# STorM32_NT_BGC_v330m.net
KiCad netlist of a schematic drawn in EAGLE
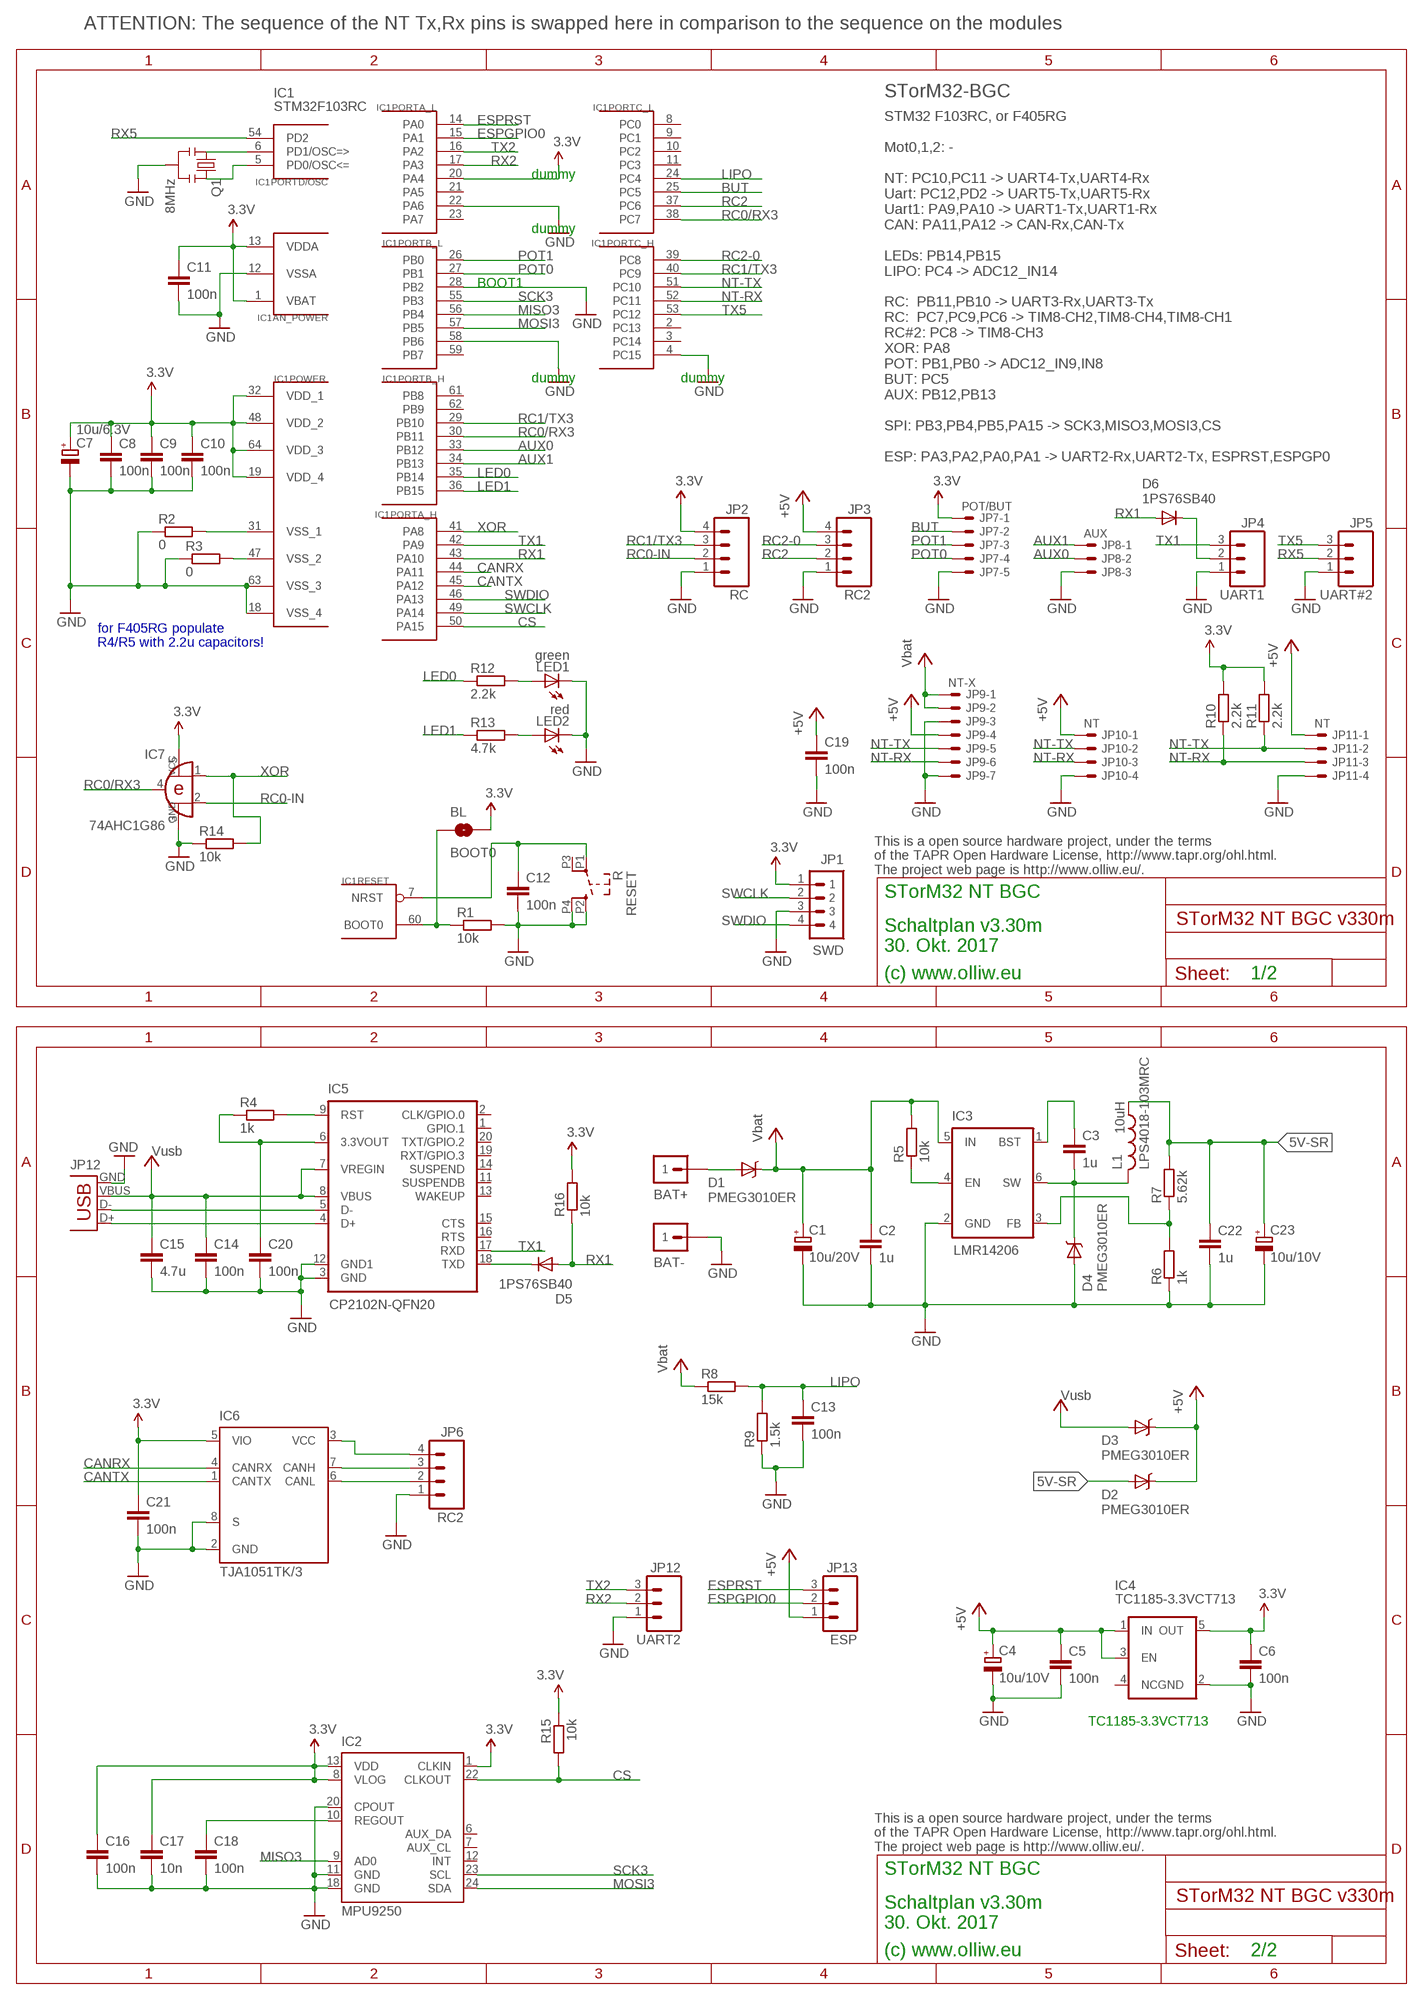
[diagram p0: schematic, sheet 1]

(export (version "E")
  (design (tool "Eeschema 10.0.6"))
  (components
    (comp (ref "BAT+")
      (value "M1X1")
      (footprint "eagle-import:1X1_WITHOUT")
      (libsource (lib "eagle-import") (part "M1X1"))
    )
    (comp (ref "BAT-")
      (value "M1X1")
      (footprint "eagle-import:1X1_WITHOUT")
      (libsource (lib "eagle-import") (part "M1X1"))
    )
    (comp (ref "BL")
      (value "BOOT0")
      (footprint "eagle-import:SJ_2S-NO")
      (libsource (lib "eagle-import") (part "SOLDERJUMPERNO"))
    )
    (comp (ref "C1")
      (value "10u/20V")
      (footprint "eagle-import:SMC_B")
      (libsource (lib "eagle-import") (part "CPOL-EUSMCB"))
    )
    (comp (ref "C2")
      (value "1u")
      (footprint "eagle-import:C0603")
      (libsource (lib "eagle-import") (part "C-EUC0603"))
    )
    (comp (ref "C3")
      (value "1u")
      (footprint "eagle-import:C0603")
      (libsource (lib "eagle-import") (part "C-EUC0603"))
    )
    (comp (ref "C4")
      (value "10u/10V")
      (footprint "eagle-import:SMC_A")
      (libsource (lib "eagle-import") (part "CPOL-EUSMCA"))
    )
    (comp (ref "C5")
      (value "100n")
      (footprint "eagle-import:C0603")
      (libsource (lib "eagle-import") (part "C-EUC0603"))
    )
    (comp (ref "C6")
      (value "100n")
      (footprint "eagle-import:C0402")
      (libsource (lib "eagle-import") (part "C-EUC0402"))
    )
    (comp (ref "C7")
      (value "10u/6.3V")
      (footprint "eagle-import:SMC_A")
      (libsource (lib "eagle-import") (part "CPOL-EUSMCA"))
    )
    (comp (ref "C8")
      (value "100n")
      (footprint "eagle-import:C0402")
      (libsource (lib "eagle-import") (part "C-EUC0402"))
    )
    (comp (ref "C9")
      (value "100n")
      (footprint "eagle-import:C0402")
      (libsource (lib "eagle-import") (part "C-EUC0402"))
    )
    (comp (ref "C10")
      (value "100n")
      (footprint "eagle-import:C0402")
      (libsource (lib "eagle-import") (part "C-EUC0402"))
    )
    (comp (ref "C11")
      (value "100n")
      (footprint "eagle-import:C0402")
      (libsource (lib "eagle-import") (part "C-EUC0402"))
    )
    (comp (ref "C12")
      (value "100n")
      (footprint "eagle-import:C0402")
      (libsource (lib "eagle-import") (part "C-EUC0402"))
    )
    (comp (ref "C13")
      (value "100n")
      (footprint "eagle-import:C0402")
      (libsource (lib "eagle-import") (part "C-EUC0402"))
    )
    (comp (ref "C14")
      (value "100n")
      (footprint "eagle-import:C0402")
      (libsource (lib "eagle-import") (part "C-EUC0402"))
    )
    (comp (ref "C15")
      (value "4.7u")
      (footprint "eagle-import:C0603")
      (libsource (lib "eagle-import") (part "C-EUC0603"))
    )
    (comp (ref "C16")
      (value "100n")
      (footprint "eagle-import:C0402")
      (libsource (lib "eagle-import") (part "C-EUC0402"))
    )
    (comp (ref "C17")
      (value "10n")
      (footprint "eagle-import:C0402")
      (libsource (lib "eagle-import") (part "C-EUC0402"))
    )
    (comp (ref "C18")
      (value "100n")
      (footprint "eagle-import:C0402")
      (libsource (lib "eagle-import") (part "C-EUC0402"))
    )
    (comp (ref "C19")
      (value "100n")
      (footprint "eagle-import:C0402")
      (libsource (lib "eagle-import") (part "C-EUC0402"))
    )
    (comp (ref "C20")
      (value "100n")
      (footprint "eagle-import:C0402")
      (libsource (lib "eagle-import") (part "C-EUC0402"))
    )
    (comp (ref "C21")
      (value "100n")
      (footprint "eagle-import:C0402")
      (libsource (lib "eagle-import") (part "C-EUC0402"))
    )
    (comp (ref "C22")
      (value "1u")
      (footprint "eagle-import:C0603")
      (libsource (lib "eagle-import") (part "C-EUC0603"))
    )
    (comp (ref "C23")
      (value "10u/10V")
      (footprint "eagle-import:SMC_A")
      (libsource (lib "eagle-import") (part "CPOL-EUSMCA"))
    )
    (comp (ref "D1")
      (value "PMEG3010ER")
      (footprint "eagle-import:SOD123W-DIODE")
      (libsource (lib "eagle-import") (part "DIODE-SCHOTTKYSOD123-W"))
    )
    (comp (ref "D2")
      (value "PMEG3010ER")
      (footprint "eagle-import:SOD123W-DIODE")
      (libsource (lib "eagle-import") (part "DIODE-SCHOTTKYSOD123-W"))
    )
    (comp (ref "D3")
      (value "PMEG3010ER")
      (footprint "eagle-import:SOD123W-DIODE")
      (libsource (lib "eagle-import") (part "DIODE-SCHOTTKYSOD123-W"))
    )
    (comp (ref "D4")
      (value "PMEG3010ER")
      (footprint "eagle-import:SOD123W-DIODE")
      (libsource (lib "eagle-import") (part "DIODE-SCHOTTKYSOD123-W"))
    )
    (comp (ref "D5")
      (value "1PS76SB40")
      (footprint "eagle-import:SOD110-R")
      (libsource (lib "eagle-import") (part "DIODE-SOD110-R"))
    )
    (comp (ref "D6")
      (value "1PS76SB40")
      (footprint "eagle-import:SOD110-R")
      (libsource (lib "eagle-import") (part "DIODE-SOD110-R"))
    )
    (comp (ref "IC1")
      (value "STM32F103RCT6")
      (footprint "eagle-import:TQFP64")
      (libsource (lib "eagle-import") (part "STM32F10XRXT6"))
    )
    (comp (ref "IC2")
      (value "MPU9250")
      (footprint "eagle-import:QFN-24-3X3")
      (libsource (lib "eagle-import") (part "IMU3000QFN-24-0.4MIL"))
    )
    (comp (ref "IC3")
      (value "LMR14206")
      (footprint "eagle-import:SOT23-6")
      (libsource (lib "eagle-import") (part "MP2359"))
    )
    (comp (ref "IC4")
      (value "TC1185-3.3VCT713")
      (footprint "eagle-import:SOT23-5")
      (libsource (lib "eagle-import") (part "V_REG_TPS76433SOT23-5"))
    )
    (comp (ref "IC5")
      (value "CP2102N-QFN20")
      (footprint "eagle-import:QFN20-CP2102N")
      (libsource (lib "eagle-import") (part "CP2102N-QFN20"))
    )
    (comp (ref "IC6")
      (value "TJA1051TK/3")
      (footprint "eagle-import:HVSON8")
      (libsource (lib "eagle-import") (part "TJA1051TK/3"))
    )
    (comp (ref "IC7")
      (value "74AHC1G86")
      (footprint "eagle-import:SOT23-5-VER1")
      (libsource (lib "eagle-import") (part "74AHC1G86"))
    )
    (comp (ref "JP1")
      (value "SWD")
      (footprint "eagle-import:4X1_1P27_OCT_BILEX")
      (libsource (lib "eagle-import") (part "P4X1_1P27-OCT_BILEX"))
    )
    (comp (ref "JP2")
      (value "RC")
      (footprint "eagle-import:1X04_NO_SILK")
      (libsource (lib "eagle-import") (part "M041X04_NO_SILK"))
    )
    (comp (ref "JP3")
      (value "RC2")
      (footprint "eagle-import:1X04_NO_SILK")
      (libsource (lib "eagle-import") (part "M041X04_NO_SILK"))
    )
    (comp (ref "JP4")
      (value "UART1")
      (footprint "eagle-import:1X03_NO_SILK")
      (libsource (lib "eagle-import") (part "M031X03_NO_SILK"))
    )
    (comp (ref "JP5")
      (value "UART#2")
      (footprint "eagle-import:1X03_NO_SILK")
      (libsource (lib "eagle-import") (part "M031X03_NO_SILK"))
    )
    (comp (ref "JP6")
      (value "RC2")
      (footprint "eagle-import:1X04_NO_SILK")
      (libsource (lib "eagle-import") (part "M041X04_NO_SILK"))
    )
    (comp (ref "JP7")
      (value "POT/BUT")
      (footprint "eagle-import:SM05B-SRSS-TB")
      (libsource (lib "eagle-import") (part "?M05B-SRSS-TBS"))
    )
    (comp (ref "JP8")
      (value "AUX")
      (footprint "eagle-import:SM03B-SRSS-TB")
      (libsource (lib "eagle-import") (part "?M03B-SRSS-TBS"))
    )
    (comp (ref "JP9")
      (value "NT-X")
      (footprint "eagle-import:SM07B-SRSS-TB")
      (libsource (lib "eagle-import") (part "?M07B-SRSS-TBS"))
    )
    (comp (ref "JP10")
      (value "NT")
      (footprint "eagle-import:SM04B-SRSS-TB")
      (libsource (lib "eagle-import") (part "?M04B-SRSS-TBS"))
    )
    (comp (ref "JP11")
      (value "NT")
      (footprint "eagle-import:SM04B-SRSS-TB")
      (libsource (lib "eagle-import") (part "?M04B-SRSS-TBS"))
    )
    (comp (ref "JP12")
      (value "UART2")
      (footprint "eagle-import:1X03_NO_SILK")
      (libsource (lib "eagle-import") (part "M031X03_NO_SILK"))
    )
    (comp (ref "JP13")
      (value "ESP")
      (footprint "eagle-import:1X03_NO_SILK")
      (libsource (lib "eagle-import") (part "M031X03_NO_SILK"))
    )
    (comp (ref "L1")
      (value "LPS4018-103MRC")
      (footprint "eagle-import:L4X4")
      (libsource (lib "eagle-import") (part "L"))
    )
    (comp (ref "LED1")
      (value "green")
      (footprint "eagle-import:CHIPLED_0603")
      (libsource (lib "eagle-import") (part "LEDCHIPLED_0603"))
    )
    (comp (ref "LED2")
      (value "red")
      (footprint "eagle-import:CHIPLED_0603")
      (libsource (lib "eagle-import") (part "LEDCHIPLED_0603"))
    )
    (comp (ref "Q1")
      (value "8MHz")
      (footprint "eagle-import:RESONATOR-SMD")
      (libsource (lib "eagle-import") (part "RESONATORSMD"))
    )
    (comp (ref "R1")
      (value "10k")
      (footprint "eagle-import:R0402")
      (libsource (lib "eagle-import") (part "R-EU_R0402"))
    )
    (comp (ref "R2")
      (value "0")
      (footprint "eagle-import:R0402")
      (libsource (lib "eagle-import") (part "R-EU_R0402"))
    )
    (comp (ref "R3")
      (value "0")
      (footprint "eagle-import:R0402")
      (libsource (lib "eagle-import") (part "R-EU_R0402"))
    )
    (comp (ref "R4")
      (value "1k")
      (footprint "eagle-import:R0402")
      (libsource (lib "eagle-import") (part "R-EU_R0402"))
    )
    (comp (ref "R5")
      (value "10k")
      (footprint "eagle-import:R0402")
      (libsource (lib "eagle-import") (part "R-EU_R0402"))
    )
    (comp (ref "R6")
      (value "1k")
      (footprint "eagle-import:R0402")
      (libsource (lib "eagle-import") (part "R-EU_R0402"))
    )
    (comp (ref "R7")
      (value "5.62k")
      (footprint "eagle-import:R0402")
      (libsource (lib "eagle-import") (part "R-EU_R0402"))
    )
    (comp (ref "R8")
      (value "15k")
      (footprint "eagle-import:R0402")
      (libsource (lib "eagle-import") (part "R-EU_R0402"))
    )
    (comp (ref "R9")
      (value "1.5k")
      (footprint "eagle-import:R0402")
      (libsource (lib "eagle-import") (part "R-EU_R0402"))
    )
    (comp (ref "R10")
      (value "2.2k")
      (footprint "eagle-import:R0402")
      (libsource (lib "eagle-import") (part "R-EU_R0402"))
    )
    (comp (ref "R11")
      (value "2.2k")
      (footprint "eagle-import:R0402")
      (libsource (lib "eagle-import") (part "R-EU_R0402"))
    )
    (comp (ref "R12")
      (value "2.2k")
      (footprint "eagle-import:R0402")
      (libsource (lib "eagle-import") (part "R-EU_R0402"))
    )
    (comp (ref "R13")
      (value "4.7k")
      (footprint "eagle-import:R0402")
      (libsource (lib "eagle-import") (part "R-EU_R0402"))
    )
    (comp (ref "R14")
      (value "10k")
      (footprint "eagle-import:R0402")
      (libsource (lib "eagle-import") (part "R-EU_R0402"))
    )
    (comp (ref "R15")
      (value "10k")
      (footprint "eagle-import:R0402")
      (libsource (lib "eagle-import") (part "R-EU_R0402"))
    )
    (comp (ref "R16")
      (value "10k")
      (footprint "eagle-import:R0402")
      (libsource (lib "eagle-import") (part "R-EU_R0402"))
    )
    (comp (ref "RESET")
      (value "R")
      (footprint "eagle-import:TACTILE-SWITCH-SMD-RIGHT-TL1014")
      (libsource (lib "eagle-import") (part "SWITCH-SMD-RIGHT-TL1014"))
    )
    (comp (ref "USB")
      (value "Amphenol 10118192-0001LF")
      (footprint "eagle-import:USB-MICROB")
      (libsource (lib "eagle-import") (part "USB-MICROB"))
    )
  )
  (nets
    (net (code "1") (name "+5V") (class "Default")
      (node (ref "C19") (pin "1") (pinfunction "1_1") (pintype "passive"))
      (node (ref "C4") (pin "+") (pinfunction "+_+") (pintype "passive"))
      (node (ref "C5") (pin "1") (pinfunction "1_1") (pintype "passive"))
      (node (ref "D2") (pin "C") (pinfunction "C_C") (pintype "passive"))
      (node (ref "D3") (pin "C") (pinfunction "C_C") (pintype "passive"))
      (node (ref "IC4") (pin "1") (pinfunction "IN_1") (pintype "power_in"))
      (node (ref "IC4") (pin "3") (pinfunction "EN_3") (pintype "input"))
      (node (ref "JP10") (pin "1") (pinfunction "S_1") (pintype "passive"))
      (node (ref "JP11") (pin "1") (pinfunction "S_1") (pintype "passive"))
      (node (ref "JP13") (pin "1") (pinfunction "1_1") (pintype "passive"))
      (node (ref "JP3") (pin "4") (pinfunction "4_4") (pintype "passive"))
      (node (ref "JP9") (pin "4") (pinfunction "S_4") (pintype "passive"))
    )
    (net (code "2") (name "/AUX0") (class "Default")
      (node (ref "IC1") (pin "33") (pinfunction "PB12_33") (pintype "bidirectional"))
      (node (ref "JP8") (pin "2") (pinfunction "S_2") (pintype "passive"))
    )
    (net (code "3") (name "/AUX1") (class "Default")
      (node (ref "IC1") (pin "34") (pinfunction "PB13_34") (pintype "bidirectional"))
      (node (ref "JP8") (pin "1") (pinfunction "S_1") (pintype "passive"))
    )
    (net (code "4") (name "/BUT") (class "Default")
      (node (ref "IC1") (pin "25") (pinfunction "PC5_25") (pintype "bidirectional"))
      (node (ref "JP7") (pin "2") (pinfunction "S_2") (pintype "passive"))
    )
    (net (code "5") (name "/CANRX") (class "Default")
      (node (ref "IC1") (pin "44") (pinfunction "PA11_44") (pintype "bidirectional"))
      (node (ref "IC6") (pin "4") (pinfunction "CANRX_4") (pintype "output"))
    )
    (net (code "6") (name "/CANTX") (class "Default")
      (node (ref "IC1") (pin "45") (pinfunction "PA12_45") (pintype "bidirectional"))
      (node (ref "IC6") (pin "1") (pinfunction "CANTX_1") (pintype "input"))
    )
    (net (code "7") (name "/CS") (class "Default")
      (node (ref "IC1") (pin "50") (pinfunction "PA15_50") (pintype "bidirectional"))
      (node (ref "IC2") (pin "22") (pinfunction "CLKOUT_22") (pintype "bidirectional"))
      (node (ref "R15") (pin "2") (pinfunction "2_2") (pintype "passive"))
    )
    (net (code "8") (name "/ESPGPIO0") (class "Default")
      (node (ref "IC1") (pin "15") (pinfunction "PA1_15") (pintype "bidirectional"))
      (node (ref "JP13") (pin "2") (pinfunction "2_2") (pintype "passive"))
    )
    (net (code "9") (name "/ESPRST") (class "Default")
      (node (ref "IC1") (pin "14") (pinfunction "PA0_14") (pintype "bidirectional"))
      (node (ref "JP13") (pin "3") (pinfunction "3_3") (pintype "passive"))
    )
    (net (code "10") (name "/LED0") (class "Default")
      (node (ref "IC1") (pin "35") (pinfunction "PB14_35") (pintype "bidirectional"))
      (node (ref "R12") (pin "1") (pinfunction "1_1") (pintype "passive"))
    )
    (net (code "11") (name "/LED1") (class "Default")
      (node (ref "IC1") (pin "36") (pinfunction "PB15_36") (pintype "bidirectional"))
      (node (ref "R13") (pin "1") (pinfunction "1_1") (pintype "passive"))
    )
    (net (code "12") (name "/LIPO") (class "Default")
      (node (ref "C13") (pin "1") (pinfunction "1_1") (pintype "passive"))
      (node (ref "IC1") (pin "24") (pinfunction "PC4_24") (pintype "bidirectional"))
      (node (ref "R8") (pin "2") (pinfunction "2_2") (pintype "passive"))
      (node (ref "R9") (pin "2") (pinfunction "2_2") (pintype "passive"))
    )
    (net (code "13") (name "/MISO3") (class "Default")
      (node (ref "IC1") (pin "56") (pinfunction "PB4_56") (pintype "bidirectional"))
      (node (ref "IC2") (pin "9") (pinfunction "AD0_9") (pintype "bidirectional"))
    )
    (net (code "14") (name "/MOSI3") (class "Default")
      (node (ref "IC1") (pin "57") (pinfunction "PB5_57") (pintype "bidirectional"))
      (node (ref "IC2") (pin "24") (pinfunction "SDA_24") (pintype "bidirectional"))
    )
    (net (code "15") (name "/NT-RX") (class "Default")
      (node (ref "IC1") (pin "52") (pinfunction "PC11_52") (pintype "bidirectional"))
      (node (ref "JP10") (pin "3") (pinfunction "S_3") (pintype "passive"))
      (node (ref "JP11") (pin "3") (pinfunction "S_3") (pintype "passive"))
      (node (ref "JP9") (pin "6") (pinfunction "S_6") (pintype "passive"))
      (node (ref "R10") (pin "1") (pinfunction "1_1") (pintype "passive"))
    )
    (net (code "16") (name "/NT-TX") (class "Default")
      (node (ref "IC1") (pin "51") (pinfunction "PC10_51") (pintype "bidirectional"))
      (node (ref "JP10") (pin "2") (pinfunction "S_2") (pintype "passive"))
      (node (ref "JP11") (pin "2") (pinfunction "S_2") (pintype "passive"))
      (node (ref "JP9") (pin "5") (pinfunction "S_5") (pintype "passive"))
      (node (ref "R11") (pin "1") (pinfunction "1_1") (pintype "passive"))
    )
    (net (code "17") (name "/POT0") (class "Default")
      (node (ref "IC1") (pin "27") (pinfunction "PB1_27") (pintype "bidirectional"))
      (node (ref "JP7") (pin "4") (pinfunction "S_4") (pintype "passive"))
    )
    (net (code "18") (name "/POT1") (class "Default")
      (node (ref "IC1") (pin "26") (pinfunction "PB0_26") (pintype "bidirectional"))
      (node (ref "JP7") (pin "3") (pinfunction "S_3") (pintype "passive"))
    )
    (net (code "19") (name "/RC0-IN") (class "Default")
      (node (ref "IC7") (pin "2") (pinfunction "I1_2") (pintype "input"))
      (node (ref "JP2") (pin "2") (pinfunction "2_2") (pintype "passive"))
    )
    (net (code "20") (name "/RC0{slash}RX3") (class "Default")
      (node (ref "IC1") (pin "30") (pinfunction "PB11_30") (pintype "bidirectional"))
      (node (ref "IC1") (pin "38") (pinfunction "PC7_38") (pintype "bidirectional"))
      (node (ref "IC7") (pin "4") (pinfunction "O_4") (pintype "output"))
    )
    (net (code "21") (name "/RC1{slash}TX3") (class "Default")
      (node (ref "IC1") (pin "29") (pinfunction "PB10_29") (pintype "bidirectional"))
      (node (ref "IC1") (pin "40") (pinfunction "PC9_40") (pintype "bidirectional"))
      (node (ref "JP2") (pin "3") (pinfunction "3_3") (pintype "passive"))
    )
    (net (code "22") (name "/RC2") (class "Default")
      (node (ref "IC1") (pin "37") (pinfunction "PC6_37") (pintype "bidirectional"))
      (node (ref "JP3") (pin "2") (pinfunction "2_2") (pintype "passive"))
    )
    (net (code "23") (name "/RC2-0") (class "Default")
      (node (ref "IC1") (pin "39") (pinfunction "PC8_39") (pintype "bidirectional"))
      (node (ref "JP3") (pin "3") (pinfunction "3_3") (pintype "passive"))
    )
    (net (code "24") (name "/RX1") (class "Default")
      (node (ref "D5") (pin "A") (pinfunction "A_A") (pintype "passive"))
      (node (ref "D6") (pin "A") (pinfunction "A_A") (pintype "passive"))
      (node (ref "IC1") (pin "43") (pinfunction "PA10_43") (pintype "bidirectional"))
      (node (ref "R16") (pin "1") (pinfunction "1_1") (pintype "passive"))
    )
    (net (code "25") (name "/RX2") (class "Default")
      (node (ref "IC1") (pin "17") (pinfunction "PA3_17") (pintype "bidirectional"))
      (node (ref "JP12") (pin "2") (pinfunction "2_2") (pintype "passive"))
    )
    (net (code "26") (name "/RX5") (class "Default")
      (node (ref "IC1") (pin "54") (pinfunction "PD2_54") (pintype "bidirectional"))
      (node (ref "JP5") (pin "2") (pinfunction "2_2") (pintype "passive"))
    )
    (net (code "27") (name "/SCK3") (class "Default")
      (node (ref "IC1") (pin "55") (pinfunction "PB3_55") (pintype "bidirectional"))
      (node (ref "IC2") (pin "23") (pinfunction "SCL_23") (pintype "bidirectional"))
    )
    (net (code "28") (name "/SWCLK") (class "Default")
      (node (ref "IC1") (pin "49") (pinfunction "PA14_49") (pintype "bidirectional"))
      (node (ref "JP1") (pin "2") (pinfunction "2_2") (pintype "passive"))
    )
    (net (code "29") (name "/SWDIO") (class "Default")
      (node (ref "IC1") (pin "46") (pinfunction "PA13_46") (pintype "bidirectional"))
      (node (ref "JP1") (pin "4") (pinfunction "4_4") (pintype "passive"))
    )
    (net (code "30") (name "/TX1") (class "Default")
      (node (ref "IC1") (pin "42") (pinfunction "PA9_42") (pintype "bidirectional"))
      (node (ref "IC5") (pin "17") (pinfunction "RXD_17") (pintype "input"))
      (node (ref "JP4") (pin "3") (pinfunction "3_3") (pintype "passive"))
    )
    (net (code "31") (name "/TX2") (class "Default")
      (node (ref "IC1") (pin "16") (pinfunction "PA2_16") (pintype "bidirectional"))
      (node (ref "JP12") (pin "3") (pinfunction "3_3") (pintype "passive"))
    )
    (net (code "32") (name "/TX5") (class "Default")
      (node (ref "IC1") (pin "53") (pinfunction "PC12_53") (pintype "bidirectional"))
      (node (ref "JP5") (pin "3") (pinfunction "3_3") (pintype "passive"))
    )
    (net (code "33") (name "/XOR") (class "Default")
      (node (ref "IC1") (pin "41") (pinfunction "PA8_41") (pintype "bidirectional"))
      (node (ref "IC7") (pin "1") (pinfunction "I0_1") (pintype "input"))
      (node (ref "R14") (pin "2") (pinfunction "2_2") (pintype "passive"))
    )
    (net (code "34") (name "3.3V") (class "Default")
      (node (ref "BL") (pin "2") (pinfunction "2_2") (pintype "passive"))
      (node (ref "C10") (pin "1") (pinfunction "1_1") (pintype "passive"))
      (node (ref "C11") (pin "1") (pinfunction "1_1") (pintype "passive"))
      (node (ref "C16") (pin "1") (pinfunction "1_1") (pintype "passive"))
      (node (ref "C17") (pin "1") (pinfunction "1_1") (pintype "passive"))
      (node (ref "C21") (pin "1") (pinfunction "1_1") (pintype "passive"))
      (node (ref "C6") (pin "1") (pinfunction "1_1") (pintype "passive"))
      (node (ref "C7") (pin "+") (pinfunction "+_+") (pintype "passive"))
      (node (ref "C8") (pin "1") (pinfunction "1_1") (pintype "passive"))
      (node (ref "C9") (pin "1") (pinfunction "1_1") (pintype "passive"))
      (node (ref "IC1") (pin "1") (pinfunction "VBAT_1") (pintype "power_in"))
      (node (ref "IC1") (pin "13") (pinfunction "VDDA_13") (pintype "power_in"))
      (node (ref "IC1") (pin "19") (pinfunction "VDD_4_19") (pintype "power_in"))
      (node (ref "IC1") (pin "20") (pinfunction "PA4_20") (pintype "bidirectional"))
      (node (ref "IC1") (pin "32") (pinfunction "VDD_1_32") (pintype "power_in"))
      (node (ref "IC1") (pin "48") (pinfunction "VDD_2_48") (pintype "power_in"))
      (node (ref "IC1") (pin "64") (pinfunction "VDD_3_64") (pintype "power_in"))
      (node (ref "IC2") (pin "1") (pinfunction "CLKIN_1") (pintype "bidirectional"))
      (node (ref "IC2") (pin "13") (pinfunction "VDD_13") (pintype "bidirectional"))
      (node (ref "IC2") (pin "8") (pinfunction "VLOG_8") (pintype "bidirectional"))
      (node (ref "IC4") (pin "5") (pinfunction "OUT_5") (pintype "output"))
      (node (ref "IC6") (pin "5") (pinfunction "VIO_5") (pintype "power_in"))
      (node (ref "IC7") (pin "5") (pinfunction "VCC_5") (pintype "power_in"))
      (node (ref "JP1") (pin "1") (pinfunction "1_1") (pintype "passive"))
      (node (ref "JP2") (pin "4") (pinfunction "4_4") (pintype "passive"))
      (node (ref "JP7") (pin "1") (pinfunction "S_1") (pintype "passive"))
      (node (ref "R10") (pin "2") (pinfunction "2_2") (pintype "passive"))
      (node (ref "R11") (pin "2") (pinfunction "2_2") (pintype "passive"))
      (node (ref "R15") (pin "1") (pinfunction "1_1") (pintype "passive"))
      (node (ref "R16") (pin "2") (pinfunction "2_2") (pintype "passive"))
    )
    (net (code "35") (name "5V-SR") (class "Default")
      (node (ref "C22") (pin "1") (pinfunction "1_1") (pintype "passive"))
      (node (ref "C23") (pin "+") (pinfunction "+_+") (pintype "passive"))
      (node (ref "D2") (pin "A") (pinfunction "A_A") (pintype "passive"))
      (node (ref "L1") (pin "1") (pinfunction "1_1") (pintype "passive"))
      (node (ref "R7") (pin "2") (pinfunction "2_2") (pintype "passive"))
    )
    (net (code "36") (name "GND") (class "Default")
      (node (ref "BAT-") (pin "1") (pinfunction "1_1") (pintype "passive"))
      (node (ref "C1") (pin "-") (pinfunction "-_-") (pintype "passive"))
      (node (ref "C10") (pin "2") (pinfunction "2_2") (pintype "passive"))
      (node (ref "C11") (pin "2") (pinfunction "2_2") (pintype "passive"))
      (node (ref "C12") (pin "2") (pinfunction "2_2") (pintype "passive"))
      (node (ref "C13") (pin "2") (pinfunction "2_2") (pintype "passive"))
      (node (ref "C14") (pin "2") (pinfunction "2_2") (pintype "passive"))
      (node (ref "C15") (pin "2") (pinfunction "2_2") (pintype "passive"))
      (node (ref "C16") (pin "2") (pinfunction "2_2") (pintype "passive"))
      (node (ref "C17") (pin "2") (pinfunction "2_2") (pintype "passive"))
      (node (ref "C18") (pin "2") (pinfunction "2_2") (pintype "passive"))
      (node (ref "C19") (pin "2") (pinfunction "2_2") (pintype "passive"))
      (node (ref "C2") (pin "2") (pinfunction "2_2") (pintype "passive"))
      (node (ref "C20") (pin "2") (pinfunction "2_2") (pintype "passive"))
      (node (ref "C21") (pin "2") (pinfunction "2_2") (pintype "passive"))
      (node (ref "C22") (pin "2") (pinfunction "2_2") (pintype "passive"))
      (node (ref "C23") (pin "-") (pinfunction "-_-") (pintype "passive"))
      (node (ref "C4") (pin "-") (pinfunction "-_-") (pintype "passive"))
      (node (ref "C5") (pin "2") (pinfunction "2_2") (pintype "passive"))
      (node (ref "C6") (pin "2") (pinfunction "2_2") (pintype "passive"))
      (node (ref "C7") (pin "-") (pinfunction "-_-") (pintype "passive"))
      (node (ref "C8") (pin "2") (pinfunction "2_2") (pintype "passive"))
      (node (ref "C9") (pin "2") (pinfunction "2_2") (pintype "passive"))
      (node (ref "D4") (pin "A") (pinfunction "A_A") (pintype "passive"))
      (node (ref "IC1") (pin "12") (pinfunction "VSSA_12") (pintype "power_in"))
      (node (ref "IC1") (pin "18") (pinfunction "VSS_4_18") (pintype "power_in"))
      (node (ref "IC1") (pin "22") (pinfunction "PA6_22") (pintype "bidirectional"))
      (node (ref "IC1") (pin "28") (pinfunction "PB2_28") (pintype "bidirectional"))
      (node (ref "IC1") (pin "4") (pinfunction "PC15_4") (pintype "bidirectional"))
      (node (ref "IC1") (pin "58") (pinfunction "PB6_58") (pintype "bidirectional"))
      (node (ref "IC1") (pin "63") (pinfunction "VSS_3_63") (pintype "power_in"))
      (node (ref "IC2") (pin "11") (pinfunction "GND_11") (pintype "bidirectional"))
      (node (ref "IC2") (pin "18") (pinfunction "GND_18") (pintype "bidirectional"))
      (node (ref "IC2") (pin "20") (pinfunction "CPOUT_20") (pintype "bidirectional"))
      (node (ref "IC3") (pin "2") (pinfunction "GND_2") (pintype "power_in"))
      (node (ref "IC4") (pin "2") (pinfunction "GND_2") (pintype "power_in"))
      (node (ref "IC5") (pin "12") (pinfunction "GND1_12") (pintype "power_in"))
      (node (ref "IC5") (pin "3") (pinfunction "GND_3") (pintype "power_in"))
      (node (ref "IC6") (pin "2") (pinfunction "GND_2") (pintype "power_in"))
      (node (ref "IC6") (pin "8") (pinfunction "S_8") (pintype "input"))
      (node (ref "IC7") (pin "3") (pinfunction "GND_3") (pintype "power_in"))
      (node (ref "JP1") (pin "3") (pinfunction "3_3") (pintype "passive"))
      (node (ref "JP10") (pin "4") (pinfunction "S_4") (pintype "passive"))
      (node (ref "JP11") (pin "4") (pinfunction "S_4") (pintype "passive"))
      (node (ref "JP12") (pin "1") (pinfunction "1_1") (pintype "passive"))
      (node (ref "JP2") (pin "1") (pinfunction "1_1") (pintype "passive"))
      (node (ref "JP3") (pin "1") (pinfunction "1_1") (pintype "passive"))
      (node (ref "JP4") (pin "1") (pinfunction "1_1") (pintype "passive"))
      (node (ref "JP5") (pin "1") (pinfunction "1_1") (pintype "passive"))
      (node (ref "JP6") (pin "1") (pinfunction "1_1") (pintype "passive"))
      (node (ref "JP7") (pin "5") (pinfunction "S_5") (pintype "passive"))
      (node (ref "JP8") (pin "3") (pinfunction "S_3") (pintype "passive"))
      (node (ref "JP9") (pin "3") (pinfunction "S_3") (pintype "passive"))
      (node (ref "JP9") (pin "7") (pinfunction "S_7") (pintype "passive"))
      (node (ref "LED1") (pin "C") (pinfunction "C_C") (pintype "passive"))
      (node (ref "LED2") (pin "C") (pinfunction "C_C") (pintype "passive"))
      (node (ref "Q1") (pin "2") (pinfunction "2_2") (pintype "passive"))
      (node (ref "R1") (pin "2") (pinfunction "2_2") (pintype "passive"))
      (node (ref "R14") (pin "1") (pinfunction "1_1") (pintype "passive"))
      (node (ref "R2") (pin "1") (pinfunction "1_1") (pintype "passive"))
      (node (ref "R3") (pin "1") (pinfunction "1_1") (pintype "passive"))
      (node (ref "R6") (pin "1") (pinfunction "1_1") (pintype "passive"))
      (node (ref "R9") (pin "1") (pinfunction "1_1") (pintype "passive"))
      (node (ref "RESET") (pin "P2") (pinfunction "1_P2") (pintype "passive"))
      (node (ref "RESET") (pin "P4") (pinfunction "2_P4") (pintype "passive"))
      (node (ref "USB") (pin "GND") (pinfunction "GND_GND") (pintype "bidirectional"))
    )
    (net (code "37") (name "Net-(BAT+-Pad1)") (class "Default")
      (node (ref "BAT+") (pin "1") (pinfunction "1_1") (pintype "passive"))
      (node (ref "D1") (pin "A") (pinfunction "A_A") (pintype "passive"))
    )
    (net (code "38") (name "Net-(D6-PadC)") (class "Default")
      (node (ref "D6") (pin "C") (pinfunction "C_C") (pintype "passive"))
      (node (ref "JP4") (pin "2") (pinfunction "2_2") (pintype "passive"))
    )
    (net (code "39") (name "Net-(IC1H-PD0{slash}OSC<=)") (class "Default")
      (node (ref "IC1") (pin "5") (pinfunction "PD0/OSC<=_5") (pintype "bidirectional"))
      (node (ref "Q1") (pin "3") (pinfunction "3_3") (pintype "passive"))
    )
    (net (code "40") (name "Net-(IC1H-PD1{slash}OSC=>)") (class "Default")
      (node (ref "IC1") (pin "6") (pinfunction "PD1/OSC=>_6") (pintype "bidirectional"))
      (node (ref "Q1") (pin "1") (pinfunction "1_1") (pintype "passive"))
    )
    (net (code "41") (name "Net-(IC1I-VSS_1)") (class "Default")
      (node (ref "IC1") (pin "31") (pinfunction "VSS_1_31") (pintype "power_in"))
      (node (ref "R2") (pin "2") (pinfunction "2_2") (pintype "passive"))
    )
    (net (code "42") (name "Net-(IC1I-VSS_2)") (class "Default")
      (node (ref "IC1") (pin "47") (pinfunction "VSS_2_47") (pintype "power_in"))
      (node (ref "R3") (pin "2") (pinfunction "2_2") (pintype "passive"))
    )
    (net (code "43") (name "Net-(IC1J-BOOT0)") (class "Default")
      (node (ref "BL") (pin "1") (pinfunction "1_1") (pintype "passive"))
      (node (ref "IC1") (pin "60") (pinfunction "BOOT0_60") (pintype "input"))
      (node (ref "R1") (pin "1") (pinfunction "1_1") (pintype "passive"))
    )
    (net (code "44") (name "Net-(IC1J-NRST)") (class "Default")
      (node (ref "C12") (pin "1") (pinfunction "1_1") (pintype "passive"))
      (node (ref "IC1") (pin "7") (pinfunction "NRST_7") (pintype "input"))
      (node (ref "RESET") (pin "P1") (pinfunction "3_P1") (pintype "passive"))
    )
    (net (code "45") (name "Net-(IC2-REGOUT)") (class "Default")
      (node (ref "C18") (pin "1") (pinfunction "1_1") (pintype "passive"))
      (node (ref "IC2") (pin "10") (pinfunction "REGOUT_10") (pintype "bidirectional"))
    )
    (net (code "46") (name "Net-(IC3-BST)") (class "Default")
      (node (ref "C3") (pin "1") (pinfunction "1_1") (pintype "passive"))
      (node (ref "IC3") (pin "1") (pinfunction "BST_1") (pintype "output"))
    )
    (net (code "47") (name "Net-(IC3-EN)") (class "Default")
      (node (ref "IC3") (pin "4") (pinfunction "EN_4") (pintype "input"))
      (node (ref "R5") (pin "1") (pinfunction "1_1") (pintype "passive"))
    )
    (net (code "48") (name "Net-(IC3-FB)") (class "Default")
      (node (ref "IC3") (pin "3") (pinfunction "FB_3") (pintype "input"))
      (node (ref "R6") (pin "2") (pinfunction "2_2") (pintype "passive"))
      (node (ref "R7") (pin "1") (pinfunction "1_1") (pintype "passive"))
    )
    (net (code "49") (name "Net-(IC3-SW)") (class "Default")
      (node (ref "C3") (pin "2") (pinfunction "2_2") (pintype "passive"))
      (node (ref "D4") (pin "C") (pinfunction "C_C") (pintype "passive"))
      (node (ref "IC3") (pin "6") (pinfunction "SW_6") (pintype "output"))
      (node (ref "L1") (pin "2") (pinfunction "2_2") (pintype "passive"))
    )
    (net (code "50") (name "Net-(IC5-3.3VOUT)") (class "Default")
      (node (ref "C20") (pin "1") (pinfunction "1_1") (pintype "passive"))
      (node (ref "IC5") (pin "6") (pinfunction "3.3VOUT_6") (pintype "power_in"))
      (node (ref "R4") (pin "1") (pinfunction "1_1") (pintype "passive"))
    )
    (net (code "51") (name "Net-(IC5-D+)") (class "Default")
      (node (ref "IC5") (pin "4") (pinfunction "D+_4") (pintype "bidirectional"))
      (node (ref "USB") (pin "D+") (pinfunction "D+_D+") (pintype "bidirectional"))
    )
    (net (code "52") (name "Net-(IC5-D-)") (class "Default")
      (node (ref "IC5") (pin "5") (pinfunction "D-_5") (pintype "bidirectional"))
      (node (ref "USB") (pin "D-") (pinfunction "D-_D-") (pintype "bidirectional"))
    )
    (net (code "53") (name "Net-(IC5-RST)") (class "Default")
      (node (ref "IC5") (pin "9") (pinfunction "RST_9") (pintype "input"))
      (node (ref "R4") (pin "2") (pinfunction "2_2") (pintype "passive"))
    )
    (net (code "54") (name "Net-(IC5-TXD)") (class "Default")
      (node (ref "D5") (pin "C") (pinfunction "C_C") (pintype "passive"))
      (node (ref "IC5") (pin "18") (pinfunction "TXD_18") (pintype "output"))
    )
    (net (code "55") (name "Net-(IC6-CANH)") (class "Default")
      (node (ref "IC6") (pin "7") (pinfunction "CANH_7") (pintype "bidirectional"))
      (node (ref "JP6") (pin "3") (pinfunction "3_3") (pintype "passive"))
    )
    (net (code "56") (name "Net-(IC6-CANL)") (class "Default")
      (node (ref "IC6") (pin "6") (pinfunction "CANL_6") (pintype "bidirectional"))
      (node (ref "JP6") (pin "2") (pinfunction "2_2") (pintype "passive"))
    )
    (net (code "57") (name "Net-(IC6-VCC)") (class "Default")
      (node (ref "IC6") (pin "3") (pinfunction "VCC_3") (pintype "power_in"))
      (node (ref "JP6") (pin "4") (pinfunction "4_4") (pintype "passive"))
    )
    (net (code "58") (name "Net-(LED1-PadA)") (class "Default")
      (node (ref "LED1") (pin "A") (pinfunction "A_A") (pintype "passive"))
      (node (ref "R12") (pin "2") (pinfunction "2_2") (pintype "passive"))
    )
    (net (code "59") (name "Net-(LED2-PadA)") (class "Default")
      (node (ref "LED2") (pin "A") (pinfunction "A_A") (pintype "passive"))
      (node (ref "R13") (pin "2") (pinfunction "2_2") (pintype "passive"))
    )
    (net (code "60") (name "Vbat") (class "Default")
      (node (ref "C1") (pin "+") (pinfunction "+_+") (pintype "passive"))
      (node (ref "C2") (pin "1") (pinfunction "1_1") (pintype "passive"))
      (node (ref "D1") (pin "C") (pinfunction "C_C") (pintype "passive"))
      (node (ref "IC3") (pin "5") (pinfunction "IN_5") (pintype "power_in"))
      (node (ref "JP9") (pin "1") (pinfunction "S_1") (pintype "passive"))
      (node (ref "JP9") (pin "2") (pinfunction "S_2") (pintype "passive"))
      (node (ref "R5") (pin "2") (pinfunction "2_2") (pintype "passive"))
      (node (ref "R8") (pin "1") (pinfunction "1_1") (pintype "passive"))
    )
    (net (code "61") (name "Vusb") (class "Default")
      (node (ref "C14") (pin "1") (pinfunction "1_1") (pintype "passive"))
      (node (ref "C15") (pin "1") (pinfunction "1_1") (pintype "passive"))
      (node (ref "D3") (pin "A") (pinfunction "A_A") (pintype "passive"))
      (node (ref "IC5") (pin "7") (pinfunction "VREGIN_7") (pintype "power_in"))
      (node (ref "IC5") (pin "8") (pinfunction "VBUS_8") (pintype "input"))
      (node (ref "USB") (pin "VBUS") (pinfunction "VBUS_VBUS") (pintype "bidirectional"))
    )
    (net (code "62") (name "unconnected-(IC1C-PA5-Pad21)") (class "Default")
      (node (ref "IC1") (pin "21") (pinfunction "PA5_21") (pintype "bidirectional"))
    )
    (net (code "63") (name "unconnected-(IC1C-PA7-Pad23)") (class "Default")
      (node (ref "IC1") (pin "23") (pinfunction "PA7_23") (pintype "bidirectional"))
    )
    (net (code "64") (name "unconnected-(IC1D-PB8-Pad61)") (class "Default")
      (node (ref "IC1") (pin "61") (pinfunction "PB8_61") (pintype "bidirectional"))
    )
    (net (code "65") (name "unconnected-(IC1D-PB9-Pad62)") (class "Default")
      (node (ref "IC1") (pin "62") (pinfunction "PB9_62") (pintype "bidirectional"))
    )
    (net (code "66") (name "unconnected-(IC1E-PB7-Pad59)") (class "Default")
      (node (ref "IC1") (pin "59") (pinfunction "PB7_59") (pintype "bidirectional"))
    )
    (net (code "67") (name "unconnected-(IC1F-PC13-Pad2)") (class "Default")
      (node (ref "IC1") (pin "2") (pinfunction "PC13_2") (pintype "bidirectional"))
    )
    (net (code "68") (name "unconnected-(IC1F-PC14-Pad3)") (class "Default")
      (node (ref "IC1") (pin "3") (pinfunction "PC14_3") (pintype "bidirectional"))
    )
    (net (code "69") (name "unconnected-(IC1G-PC0-Pad8)") (class "Default")
      (node (ref "IC1") (pin "8") (pinfunction "PC0_8") (pintype "bidirectional"))
    )
    (net (code "70") (name "unconnected-(IC1G-PC1-Pad9)") (class "Default")
      (node (ref "IC1") (pin "9") (pinfunction "PC1_9") (pintype "bidirectional"))
    )
    (net (code "71") (name "unconnected-(IC1G-PC2-Pad10)") (class "Default")
      (node (ref "IC1") (pin "10") (pinfunction "PC2_10") (pintype "bidirectional"))
    )
    (net (code "72") (name "unconnected-(IC1G-PC3-Pad11)") (class "Default")
      (node (ref "IC1") (pin "11") (pinfunction "PC3_11") (pintype "bidirectional"))
    )
    (net (code "73") (name "unconnected-(IC2-AUX_CL-Pad7)") (class "Default")
      (node (ref "IC2") (pin "7") (pinfunction "AUX_CL_7") (pintype "bidirectional"))
    )
    (net (code "74") (name "unconnected-(IC2-AUX_DA-Pad6)") (class "Default")
      (node (ref "IC2") (pin "6") (pinfunction "AUX_DA_6") (pintype "bidirectional"))
    )
    (net (code "75") (name "unconnected-(IC2-INT-Pad12)") (class "Default")
      (node (ref "IC2") (pin "12") (pinfunction "INT_12") (pintype "bidirectional"))
    )
    (net (code "76") (name "unconnected-(IC4-NC-Pad4)") (class "Default")
      (node (ref "IC4") (pin "4") (pinfunction "NC_4") (pintype "passive"))
    )
    (net (code "77") (name "unconnected-(IC5-CLK{slash}GPIO.0-Pad2)") (class "Default")
      (node (ref "IC5") (pin "2") (pinfunction "CLK/GPIO.0_2") (pintype "bidirectional"))
    )
    (net (code "78") (name "unconnected-(IC5-CTS-Pad15)") (class "Default")
      (node (ref "IC5") (pin "15") (pinfunction "CTS_15") (pintype "input"))
    )
    (net (code "79") (name "unconnected-(IC5-GPIO.1-Pad1)") (class "Default")
      (node (ref "IC5") (pin "1") (pinfunction "GPIO.1_1") (pintype "bidirectional"))
    )
    (net (code "80") (name "unconnected-(IC5-RTS-Pad16)") (class "Default")
      (node (ref "IC5") (pin "16") (pinfunction "RTS_16") (pintype "output"))
    )
    (net (code "81") (name "unconnected-(IC5-RXT{slash}GPIO.3-Pad19)") (class "Default")
      (node (ref "IC5") (pin "19") (pinfunction "RXT/GPIO.3_19") (pintype "bidirectional"))
    )
    (net (code "82") (name "unconnected-(IC5-SUSPEND-Pad14)") (class "Default")
      (node (ref "IC5") (pin "14") (pinfunction "SUSPEND_14") (pintype "output"))
    )
    (net (code "83") (name "unconnected-(IC5-SUSPENDB-Pad11)") (class "Default")
      (node (ref "IC5") (pin "11") (pinfunction "SUSPENDB_11") (pintype "output"))
    )
    (net (code "84") (name "unconnected-(IC5-TXT{slash}GPIO.2-Pad20)") (class "Default")
      (node (ref "IC5") (pin "20") (pinfunction "TXT/GPIO.2_20") (pintype "bidirectional"))
    )
    (net (code "85") (name "unconnected-(IC5-WAKEUP-Pad13)") (class "Default")
      (node (ref "IC5") (pin "13") (pinfunction "WAKEUP_13") (pintype "input"))
    )
    (net (code "86") (name "unconnected-(RESET-4-PadP3)") (class "Default")
      (node (ref "RESET") (pin "P3") (pinfunction "4_P3") (pintype "passive"))
    )
  )
)
